# Nucleo.net
KiCad netlist of a schematic drawn in Altium Designer
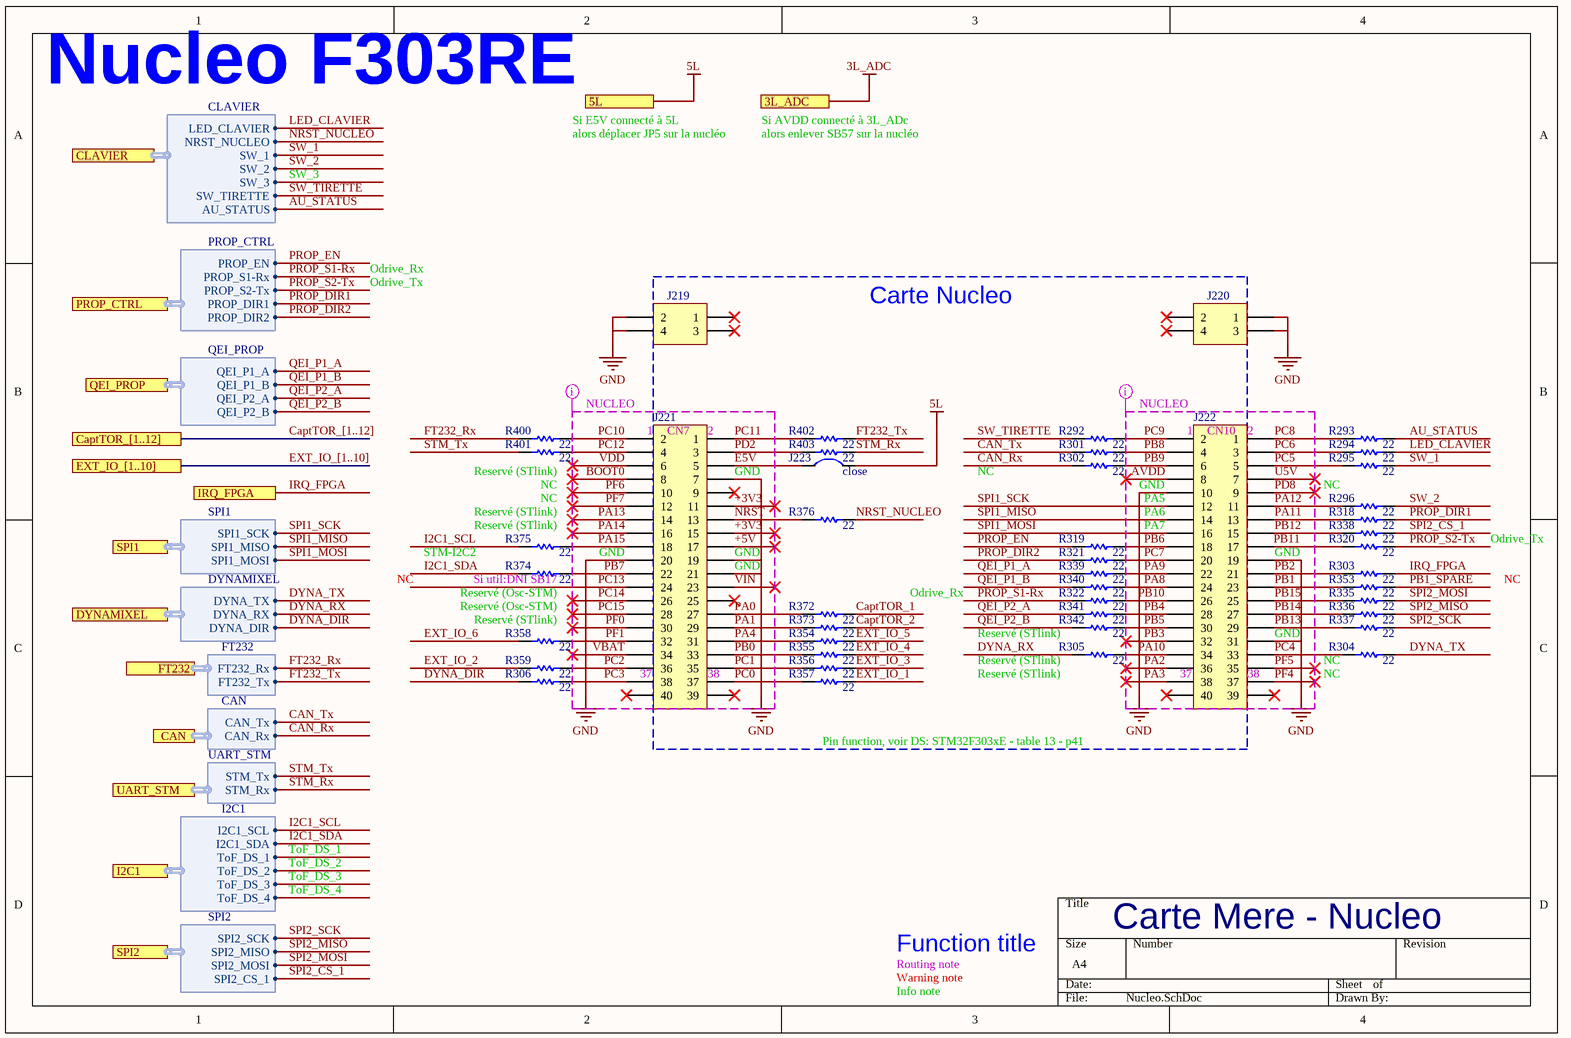
[diagram p0: Nucleo.SchDoc]

(export (version "E")
  (design (tool "Eeschema 10.0.6"))
  (components
    (comp (ref "J219")
      (value "61000421821")
      (footprint "61000421821")
      (description "WR-PHD Socket Header, SMT, pitch 2.54mm, Dual Row, Vertical, 4p")
      (fields (field (name "MANUFACTURER") "Wurth Elektronik"))
      (libsource (lib "Connecteurs") (part "61000421821"))
    )
    (comp (ref "J220")
      (value "61000421821")
      (footprint "61000421821")
      (description "WR-PHD Socket Header, SMT, pitch 2.54mm, Dual Row, Vertical, 4p")
      (fields (field (name "MANUFACTURER") "Wurth Elektronik"))
      (libsource (lib "Connecteurs") (part "61000421821"))
    )
    (comp (ref "J221")
      (value "61004021821")
      (footprint "61004021821")
      (description "WR-PHD Socket Header, SMT, pitch 2.54mm, Dual Row, Vertical, 40p")
      (fields (field (name "MANUFACTURER") "Wurth Elektronik"))
      (libsource (lib "Connecteurs") (part "61004021821"))
    )
    (comp (ref "J222")
      (value "61004021821")
      (footprint "61004021821")
      (description "WR-PHD Socket Header, SMT, pitch 2.54mm, Dual Row, Vertical, 40p")
      (fields (field (name "MANUFACTURER") "Wurth Elektronik"))
      (libsource (lib "Connecteurs") (part "61004021821"))
    )
    (comp (ref "J223")
      (value "close")
      (footprint "CAVALIER_0603_C")
      (description "Cavalier soudure \"fermé\" + empreinte dipole 0603")
      (libsource (lib "Divers") (part "CAVALIER_0603_C"))
    )
    (comp (ref "R292")
      (value "22")
      (footprint "RESC1005X04N")
      (description "RES SMD 22 OHM 1% 1/16W 0402")
      (fields (field (name "POWER") "63mW") (field (name "MANUFACTURER") "Yageo"))
      (libsource (lib "Resistance") (part "RC0402FR-0722RL"))
    )
    (comp (ref "R293")
      (value "22")
      (footprint "RESC1005X04N")
      (description "RES SMD 22 OHM 1% 1/16W 0402")
      (fields (field (name "POWER") "63mW") (field (name "MANUFACTURER") "Yageo"))
      (libsource (lib "Resistance") (part "RC0402FR-0722RL"))
    )
    (comp (ref "R294")
      (value "22")
      (footprint "RESC1005X04N")
      (description "RES SMD 22 OHM 1% 1/16W 0402")
      (fields (field (name "POWER") "63mW") (field (name "MANUFACTURER") "Yageo"))
      (libsource (lib "Resistance") (part "RC0402FR-0722RL"))
    )
    (comp (ref "R295")
      (value "22")
      (footprint "RESC1005X04N")
      (description "RES SMD 22 OHM 1% 1/16W 0402")
      (fields (field (name "POWER") "63mW") (field (name "MANUFACTURER") "Yageo"))
      (libsource (lib "Resistance") (part "RC0402FR-0722RL"))
    )
    (comp (ref "R296")
      (value "22")
      (footprint "RESC1005X04N")
      (description "RES SMD 22 OHM 1% 1/16W 0402")
      (fields (field (name "POWER") "63mW") (field (name "MANUFACTURER") "Yageo"))
      (libsource (lib "Resistance") (part "RC0402FR-0722RL"))
    )
    (comp (ref "R301")
      (value "22")
      (footprint "RESC1005X04N")
      (description "RES SMD 22 OHM 1% 1/16W 0402")
      (fields (field (name "POWER") "63mW") (field (name "MANUFACTURER") "Yageo"))
      (libsource (lib "Resistance") (part "RC0402FR-0722RL"))
    )
    (comp (ref "R302")
      (value "22")
      (footprint "RESC1005X04N")
      (description "RES SMD 22 OHM 1% 1/16W 0402")
      (fields (field (name "POWER") "63mW") (field (name "MANUFACTURER") "Yageo"))
      (libsource (lib "Resistance") (part "RC0402FR-0722RL"))
    )
    (comp (ref "R303")
      (value "22")
      (footprint "RESC1005X04N")
      (description "RES SMD 22 OHM 1% 1/16W 0402")
      (fields (field (name "POWER") "63mW") (field (name "MANUFACTURER") "Yageo"))
      (libsource (lib "Resistance") (part "RC0402FR-0722RL"))
    )
    (comp (ref "R304")
      (value "22")
      (footprint "RESC1005X04N")
      (description "RES SMD 22 OHM 1% 1/16W 0402")
      (fields (field (name "POWER") "63mW") (field (name "MANUFACTURER") "Yageo"))
      (libsource (lib "Resistance") (part "RC0402FR-0722RL"))
    )
    (comp (ref "R305")
      (value "22")
      (footprint "RESC1005X04N")
      (description "RES SMD 22 OHM 1% 1/16W 0402")
      (fields (field (name "POWER") "63mW") (field (name "MANUFACTURER") "Yageo"))
      (libsource (lib "Resistance") (part "RC0402FR-0722RL"))
    )
    (comp (ref "R306")
      (value "22")
      (footprint "RESC1005X04N")
      (description "RES SMD 22 OHM 1% 1/16W 0402")
      (fields (field (name "POWER") "63mW") (field (name "MANUFACTURER") "Yageo"))
      (libsource (lib "Resistance") (part "RC0402FR-0722RL"))
    )
    (comp (ref "R318")
      (value "22")
      (footprint "RESC1005X04N")
      (description "RES SMD 22 OHM 1% 1/16W 0402")
      (fields (field (name "POWER") "63mW") (field (name "MANUFACTURER") "Yageo"))
      (libsource (lib "Resistance") (part "RC0402FR-0722RL"))
    )
    (comp (ref "R319")
      (value "22")
      (footprint "RESC1005X04N")
      (description "RES SMD 22 OHM 1% 1/16W 0402")
      (fields (field (name "POWER") "63mW") (field (name "MANUFACTURER") "Yageo"))
      (libsource (lib "Resistance") (part "RC0402FR-0722RL"))
    )
    (comp (ref "R320")
      (value "22")
      (footprint "RESC1005X04N")
      (description "RES SMD 22 OHM 1% 1/16W 0402")
      (fields (field (name "POWER") "63mW") (field (name "MANUFACTURER") "Yageo"))
      (libsource (lib "Resistance") (part "RC0402FR-0722RL"))
    )
    (comp (ref "R321")
      (value "22")
      (footprint "RESC1005X04N")
      (description "RES SMD 22 OHM 1% 1/16W 0402")
      (fields (field (name "POWER") "63mW") (field (name "MANUFACTURER") "Yageo"))
      (libsource (lib "Resistance") (part "RC0402FR-0722RL"))
    )
    (comp (ref "R322")
      (value "22")
      (footprint "RESC1005X04N")
      (description "RES SMD 22 OHM 1% 1/16W 0402")
      (fields (field (name "POWER") "63mW") (field (name "MANUFACTURER") "Yageo"))
      (libsource (lib "Resistance") (part "RC0402FR-0722RL"))
    )
    (comp (ref "R335")
      (value "22")
      (footprint "RESC1005X04N")
      (description "RES SMD 22 OHM 1% 1/16W 0402")
      (fields (field (name "POWER") "63mW") (field (name "MANUFACTURER") "Yageo"))
      (libsource (lib "Resistance") (part "RC0402FR-0722RL"))
    )
    (comp (ref "R336")
      (value "22")
      (footprint "RESC1005X04N")
      (description "RES SMD 22 OHM 1% 1/16W 0402")
      (fields (field (name "POWER") "63mW") (field (name "MANUFACTURER") "Yageo"))
      (libsource (lib "Resistance") (part "RC0402FR-0722RL"))
    )
    (comp (ref "R337")
      (value "22")
      (footprint "RESC1005X04N")
      (description "RES SMD 22 OHM 1% 1/16W 0402")
      (fields (field (name "POWER") "63mW") (field (name "MANUFACTURER") "Yageo"))
      (libsource (lib "Resistance") (part "RC0402FR-0722RL"))
    )
    (comp (ref "R338")
      (value "22")
      (footprint "RESC1005X04N")
      (description "RES SMD 22 OHM 1% 1/16W 0402")
      (fields (field (name "POWER") "63mW") (field (name "MANUFACTURER") "Yageo"))
      (libsource (lib "Resistance") (part "RC0402FR-0722RL"))
    )
    (comp (ref "R339")
      (value "22")
      (footprint "RESC1005X04N")
      (description "RES SMD 22 OHM 1% 1/16W 0402")
      (fields (field (name "POWER") "63mW") (field (name "MANUFACTURER") "Yageo"))
      (libsource (lib "Resistance") (part "RC0402FR-0722RL"))
    )
    (comp (ref "R340")
      (value "22")
      (footprint "RESC1005X04N")
      (description "RES SMD 22 OHM 1% 1/16W 0402")
      (fields (field (name "POWER") "63mW") (field (name "MANUFACTURER") "Yageo"))
      (libsource (lib "Resistance") (part "RC0402FR-0722RL"))
    )
    (comp (ref "R341")
      (value "22")
      (footprint "RESC1005X04N")
      (description "RES SMD 22 OHM 1% 1/16W 0402")
      (fields (field (name "POWER") "63mW") (field (name "MANUFACTURER") "Yageo"))
      (libsource (lib "Resistance") (part "RC0402FR-0722RL"))
    )
    (comp (ref "R342")
      (value "22")
      (footprint "RESC1005X04N")
      (description "RES SMD 22 OHM 1% 1/16W 0402")
      (fields (field (name "POWER") "63mW") (field (name "MANUFACTURER") "Yageo"))
      (libsource (lib "Resistance") (part "RC0402FR-0722RL"))
    )
    (comp (ref "R353")
      (value "22")
      (footprint "RESC1005X04N")
      (description "RES SMD 22 OHM 1% 1/16W 0402")
      (fields (field (name "POWER") "63mW") (field (name "MANUFACTURER") "Yageo"))
      (libsource (lib "Resistance") (part "RC0402FR-0722RL"))
    )
    (comp (ref "R354")
      (value "22")
      (footprint "RESC1005X04N")
      (description "RES SMD 22 OHM 1% 1/16W 0402")
      (fields (field (name "POWER") "63mW") (field (name "MANUFACTURER") "Yageo"))
      (libsource (lib "Resistance") (part "RC0402FR-0722RL"))
    )
    (comp (ref "R355")
      (value "22")
      (footprint "RESC1005X04N")
      (description "RES SMD 22 OHM 1% 1/16W 0402")
      (fields (field (name "POWER") "63mW") (field (name "MANUFACTURER") "Yageo"))
      (libsource (lib "Resistance") (part "RC0402FR-0722RL"))
    )
    (comp (ref "R356")
      (value "22")
      (footprint "RESC1005X04N")
      (description "RES SMD 22 OHM 1% 1/16W 0402")
      (fields (field (name "POWER") "63mW") (field (name "MANUFACTURER") "Yageo"))
      (libsource (lib "Resistance") (part "RC0402FR-0722RL"))
    )
    (comp (ref "R357")
      (value "22")
      (footprint "RESC1005X04N")
      (description "RES SMD 22 OHM 1% 1/16W 0402")
      (fields (field (name "POWER") "63mW") (field (name "MANUFACTURER") "Yageo"))
      (libsource (lib "Resistance") (part "RC0402FR-0722RL"))
    )
    (comp (ref "R358")
      (value "22")
      (footprint "RESC1005X04N")
      (description "RES SMD 22 OHM 1% 1/16W 0402")
      (fields (field (name "POWER") "63mW") (field (name "MANUFACTURER") "Yageo"))
      (libsource (lib "Resistance") (part "RC0402FR-0722RL"))
    )
    (comp (ref "R359")
      (value "22")
      (footprint "RESC1005X04N")
      (description "RES SMD 22 OHM 1% 1/16W 0402")
      (fields (field (name "POWER") "63mW") (field (name "MANUFACTURER") "Yageo"))
      (libsource (lib "Resistance") (part "RC0402FR-0722RL"))
    )
    (comp (ref "R372")
      (value "22")
      (footprint "RESC1005X04N")
      (description "RES SMD 22 OHM 1% 1/16W 0402")
      (fields (field (name "POWER") "63mW") (field (name "MANUFACTURER") "Yageo"))
      (libsource (lib "Resistance") (part "RC0402FR-0722RL"))
    )
    (comp (ref "R373")
      (value "22")
      (footprint "RESC1005X04N")
      (description "RES SMD 22 OHM 1% 1/16W 0402")
      (fields (field (name "POWER") "63mW") (field (name "MANUFACTURER") "Yageo"))
      (libsource (lib "Resistance") (part "RC0402FR-0722RL"))
    )
    (comp (ref "R374")
      (value "22")
      (footprint "RESC1005X04N")
      (description "RES SMD 22 OHM 1% 1/16W 0402")
      (fields (field (name "POWER") "63mW") (field (name "MANUFACTURER") "Yageo"))
      (libsource (lib "Resistance") (part "RC0402FR-0722RL"))
    )
    (comp (ref "R375")
      (value "22")
      (footprint "RESC1005X04N")
      (description "RES SMD 22 OHM 1% 1/16W 0402")
      (fields (field (name "POWER") "63mW") (field (name "MANUFACTURER") "Yageo"))
      (libsource (lib "Resistance") (part "RC0402FR-0722RL"))
    )
    (comp (ref "R376")
      (value "22")
      (footprint "RESC1005X04N")
      (description "RES SMD 22 OHM 1% 1/16W 0402")
      (fields (field (name "POWER") "63mW") (field (name "MANUFACTURER") "Yageo"))
      (libsource (lib "Resistance") (part "RC0402FR-0722RL"))
    )
    (comp (ref "R400")
      (value "22")
      (footprint "RESC1005X04N")
      (description "RES SMD 22 OHM 1% 1/16W 0402")
      (fields (field (name "POWER") "63mW") (field (name "MANUFACTURER") "Yageo"))
      (libsource (lib "Resistance") (part "RC0402FR-0722RL"))
    )
    (comp (ref "R401")
      (value "22")
      (footprint "RESC1005X04N")
      (description "RES SMD 22 OHM 1% 1/16W 0402")
      (fields (field (name "POWER") "63mW") (field (name "MANUFACTURER") "Yageo"))
      (libsource (lib "Resistance") (part "RC0402FR-0722RL"))
    )
    (comp (ref "R402")
      (value "22")
      (footprint "RESC1005X04N")
      (description "RES SMD 22 OHM 1% 1/16W 0402")
      (fields (field (name "POWER") "63mW") (field (name "MANUFACTURER") "Yageo"))
      (libsource (lib "Resistance") (part "RC0402FR-0722RL"))
    )
    (comp (ref "R403")
      (value "22")
      (footprint "RESC1005X04N")
      (description "RES SMD 22 OHM 1% 1/16W 0402")
      (fields (field (name "POWER") "63mW") (field (name "MANUFACTURER") "Yageo"))
      (libsource (lib "Resistance") (part "RC0402FR-0722RL"))
    )
  )
  (nets
    (net (code "25") (name "/+3V3") (class "Default")
      (node (ref "J221") (pin "11") (pinfunction "11_11") (pintype "passive"))
      (node (ref "J221") (pin "15") (pinfunction "15_15") (pintype "passive"))
    )
    (net (code "26") (name "/+5V") (class "Default")
      (node (ref "J221") (pin "17") (pinfunction "17_17") (pintype "passive+no_connect"))
    )
    (net (code "27") (name "/AU_STATUS") (class "Default")
      (node (ref "R293") (pin "2") (pinfunction "2_2") (pintype "passive"))
    )
    (net (code "28") (name "/AVDD") (class "Default")
      (node (ref "J222") (pin "8") (pinfunction "8_8") (pintype "passive+no_connect"))
    )
    (net (code "29") (name "/BOOT0") (class "Default")
      (node (ref "J221") (pin "8") (pinfunction "8_8") (pintype "passive+no_connect"))
    )
    (net (code "30") (name "/CAN_Rx") (class "Default")
      (node (ref "R302") (pin "1") (pinfunction "1_1") (pintype "passive"))
    )
    (net (code "31") (name "/CAN_Tx") (class "Default")
      (node (ref "R301") (pin "1") (pinfunction "1_1") (pintype "passive"))
    )
    (net (code "32") (name "/CaptTOR_1") (class "Default")
      (node (ref "R372") (pin "2") (pinfunction "2_2") (pintype "passive"))
    )
    (net (code "33") (name "/CaptTOR_2") (class "Default")
      (node (ref "R373") (pin "2") (pinfunction "2_2") (pintype "passive"))
    )
    (net (code "35") (name "/DYNA_DIR") (class "Default")
      (node (ref "R306") (pin "1") (pinfunction "1_1") (pintype "passive"))
    )
    (net (code "36") (name "/DYNA_RX") (class "Default")
      (node (ref "R305") (pin "1") (pinfunction "1_1") (pintype "passive"))
    )
    (net (code "37") (name "/DYNA_TX") (class "Default")
      (node (ref "R304") (pin "2") (pinfunction "2_2") (pintype "passive"))
    )
    (net (code "38") (name "/E5V") (class "Default")
      (node (ref "J221") (pin "5") (pinfunction "5_5") (pintype "passive"))
      (node (ref "J223") (pin "1") (pinfunction "1_1") (pintype "passive"))
    )
    (net (code "39") (name "/EXT_IO_1") (class "Default")
      (node (ref "R357") (pin "2") (pinfunction "2_2") (pintype "passive"))
    )
    (net (code "40") (name "/EXT_IO_2") (class "Default")
      (node (ref "R359") (pin "1") (pinfunction "1_1") (pintype "passive"))
    )
    (net (code "41") (name "/EXT_IO_3") (class "Default")
      (node (ref "R356") (pin "2") (pinfunction "2_2") (pintype "passive"))
    )
    (net (code "42") (name "/EXT_IO_4") (class "Default")
      (node (ref "R355") (pin "2") (pinfunction "2_2") (pintype "passive"))
    )
    (net (code "43") (name "/EXT_IO_5") (class "Default")
      (node (ref "R354") (pin "2") (pinfunction "2_2") (pintype "passive"))
    )
    (net (code "44") (name "/EXT_IO_6") (class "Default")
      (node (ref "R358") (pin "1") (pinfunction "1_1") (pintype "passive"))
    )
    (net (code "46") (name "/FT232_Rx") (class "Default")
      (node (ref "R400") (pin "1") (pinfunction "1_1") (pintype "passive"))
    )
    (net (code "47") (name "/FT232_Tx") (class "Default")
      (node (ref "R402") (pin "2") (pinfunction "2_2") (pintype "passive"))
    )
    (net (code "48") (name "/I2C1_SCL") (class "Default")
      (node (ref "R375") (pin "1") (pinfunction "1_1") (pintype "passive"))
    )
    (net (code "49") (name "/I2C1_SDA") (class "Default")
      (node (ref "R374") (pin "1") (pinfunction "1_1") (pintype "passive"))
    )
    (net (code "50") (name "/IRQ_FPGA") (class "Default")
      (node (ref "R303") (pin "2") (pinfunction "2_2") (pintype "passive"))
    )
    (net (code "51") (name "/LED_CLAVIER") (class "Default")
      (node (ref "R294") (pin "2") (pinfunction "2_2") (pintype "passive"))
    )
    (net (code "52") (name "/NRST") (class "Default")
      (node (ref "J221") (pin "13") (pinfunction "13_13") (pintype "passive"))
      (node (ref "R376") (pin "1") (pinfunction "1_1") (pintype "passive"))
    )
    (net (code "53") (name "/NRST_NUCLEO") (class "Default")
      (node (ref "R376") (pin "2") (pinfunction "2_2") (pintype "passive"))
    )
    (net (code "54") (name "/PA0") (class "Default")
      (node (ref "J221") (pin "27") (pinfunction "27_27") (pintype "passive"))
      (node (ref "R372") (pin "1") (pinfunction "1_1") (pintype "passive"))
    )
    (net (code "55") (name "/PA1") (class "Default")
      (node (ref "J221") (pin "29") (pinfunction "29_29") (pintype "passive"))
      (node (ref "R373") (pin "1") (pinfunction "1_1") (pintype "passive"))
    )
    (net (code "56") (name "/PA2") (class "Default")
      (node (ref "J222") (pin "36") (pinfunction "36_36") (pintype "passive+no_connect"))
    )
    (net (code "57") (name "/PA3") (class "Default")
      (node (ref "J222") (pin "38") (pinfunction "38_38") (pintype "passive+no_connect"))
    )
    (net (code "58") (name "/PA4") (class "Default")
      (node (ref "J221") (pin "31") (pinfunction "31_31") (pintype "passive"))
      (node (ref "R354") (pin "1") (pinfunction "1_1") (pintype "passive"))
    )
    (net (code "59") (name "/PA8") (class "Default")
      (node (ref "J222") (pin "24") (pinfunction "24_24") (pintype "passive"))
      (node (ref "R340") (pin "2") (pinfunction "2_2") (pintype "passive"))
    )
    (net (code "60") (name "/PA9") (class "Default")
      (node (ref "J222") (pin "22") (pinfunction "22_22") (pintype "passive"))
      (node (ref "R339") (pin "2") (pinfunction "2_2") (pintype "passive"))
    )
    (net (code "61") (name "/PA10") (class "Default")
      (node (ref "J222") (pin "34") (pinfunction "34_34") (pintype "passive"))
      (node (ref "R305") (pin "2") (pinfunction "2_2") (pintype "passive"))
    )
    (net (code "62") (name "/PA11") (class "Default")
      (node (ref "J222") (pin "13") (pinfunction "13_13") (pintype "passive"))
      (node (ref "R318") (pin "1") (pinfunction "1_1") (pintype "passive"))
    )
    (net (code "63") (name "/PA12") (class "Default")
      (node (ref "J222") (pin "11") (pinfunction "11_11") (pintype "passive"))
      (node (ref "R296") (pin "1") (pinfunction "1_1") (pintype "passive"))
    )
    (net (code "64") (name "/PA13") (class "Default")
      (node (ref "J221") (pin "14") (pinfunction "14_14") (pintype "passive+no_connect"))
    )
    (net (code "65") (name "/PA14") (class "Default")
      (node (ref "J221") (pin "16") (pinfunction "16_16") (pintype "passive+no_connect"))
    )
    (net (code "66") (name "/PA15") (class "Default")
      (node (ref "J221") (pin "18") (pinfunction "18_18") (pintype "passive"))
      (node (ref "R375") (pin "2") (pinfunction "2_2") (pintype "passive"))
    )
    (net (code "67") (name "/PB0") (class "Default")
      (node (ref "J221") (pin "33") (pinfunction "33_33") (pintype "passive"))
      (node (ref "R355") (pin "1") (pinfunction "1_1") (pintype "passive"))
    )
    (net (code "68") (name "/PB1") (class "Default")
      (node (ref "J222") (pin "23") (pinfunction "23_23") (pintype "passive"))
      (node (ref "R353") (pin "1") (pinfunction "1_1") (pintype "passive"))
    )
    (net (code "69") (name "/PB1_SPARE") (class "Default")
      (node (ref "R353") (pin "2") (pinfunction "2_2") (pintype "passive"))
    )
    (net (code "70") (name "/PB2") (class "Default")
      (node (ref "J222") (pin "21") (pinfunction "21_21") (pintype "passive"))
      (node (ref "R303") (pin "1") (pinfunction "1_1") (pintype "passive"))
    )
    (net (code "71") (name "/PB3") (class "Default")
      (node (ref "J222") (pin "32") (pinfunction "32_32") (pintype "passive+no_connect"))
    )
    (net (code "72") (name "/PB4") (class "Default")
      (node (ref "J222") (pin "28") (pinfunction "28_28") (pintype "passive"))
      (node (ref "R341") (pin "2") (pinfunction "2_2") (pintype "passive"))
    )
    (net (code "73") (name "/PB5") (class "Default")
      (node (ref "J222") (pin "30") (pinfunction "30_30") (pintype "passive"))
      (node (ref "R342") (pin "2") (pinfunction "2_2") (pintype "passive"))
    )
    (net (code "74") (name "/PB6") (class "Default")
      (node (ref "J222") (pin "18") (pinfunction "18_18") (pintype "passive"))
      (node (ref "R319") (pin "2") (pinfunction "2_2") (pintype "passive"))
    )
    (net (code "75") (name "/PB7") (class "Default")
      (node (ref "J221") (pin "22") (pinfunction "22_22") (pintype "passive"))
      (node (ref "R374") (pin "2") (pinfunction "2_2") (pintype "passive"))
    )
    (net (code "76") (name "/PB8") (class "Default")
      (node (ref "J222") (pin "4") (pinfunction "4_4") (pintype "passive"))
      (node (ref "R301") (pin "2") (pinfunction "2_2") (pintype "passive"))
    )
    (net (code "77") (name "/PB9") (class "Default")
      (node (ref "J222") (pin "6") (pinfunction "6_6") (pintype "passive"))
      (node (ref "R302") (pin "2") (pinfunction "2_2") (pintype "passive"))
    )
    (net (code "78") (name "/PB10") (class "Default")
      (node (ref "J222") (pin "26") (pinfunction "26_26") (pintype "passive"))
      (node (ref "R322") (pin "2") (pinfunction "2_2") (pintype "passive"))
    )
    (net (code "79") (name "/PB11") (class "Default")
      (node (ref "J222") (pin "17") (pinfunction "17_17") (pintype "passive"))
      (node (ref "R320") (pin "1") (pinfunction "1_1") (pintype "passive"))
    )
    (net (code "80") (name "/PB12") (class "Default")
      (node (ref "J222") (pin "15") (pinfunction "15_15") (pintype "passive"))
      (node (ref "R338") (pin "1") (pinfunction "1_1") (pintype "passive"))
    )
    (net (code "81") (name "/PB13") (class "Default")
      (node (ref "J222") (pin "29") (pinfunction "29_29") (pintype "passive"))
      (node (ref "R337") (pin "1") (pinfunction "1_1") (pintype "passive"))
    )
    (net (code "82") (name "/PB14") (class "Default")
      (node (ref "J222") (pin "27") (pinfunction "27_27") (pintype "passive"))
      (node (ref "R336") (pin "1") (pinfunction "1_1") (pintype "passive"))
    )
    (net (code "83") (name "/PB15") (class "Default")
      (node (ref "J222") (pin "25") (pinfunction "25_25") (pintype "passive"))
      (node (ref "R335") (pin "1") (pinfunction "1_1") (pintype "passive"))
    )
    (net (code "84") (name "/PC0") (class "Default")
      (node (ref "J221") (pin "37") (pinfunction "37_37") (pintype "passive"))
      (node (ref "R357") (pin "1") (pinfunction "1_1") (pintype "passive"))
    )
    (net (code "85") (name "/PC1") (class "Default")
      (node (ref "J221") (pin "35") (pinfunction "35_35") (pintype "passive"))
      (node (ref "R356") (pin "1") (pinfunction "1_1") (pintype "passive"))
    )
    (net (code "86") (name "/PC2") (class "Default")
      (node (ref "J221") (pin "36") (pinfunction "36_36") (pintype "passive"))
      (node (ref "R359") (pin "2") (pinfunction "2_2") (pintype "passive"))
    )
    (net (code "87") (name "/PC3") (class "Default")
      (node (ref "J221") (pin "38") (pinfunction "38_38") (pintype "passive"))
      (node (ref "R306") (pin "2") (pinfunction "2_2") (pintype "passive"))
    )
    (net (code "88") (name "/PC4") (class "Default")
      (node (ref "J222") (pin "33") (pinfunction "33_33") (pintype "passive"))
      (node (ref "R304") (pin "1") (pinfunction "1_1") (pintype "passive"))
    )
    (net (code "89") (name "/PC5") (class "Default")
      (node (ref "J222") (pin "5") (pinfunction "5_5") (pintype "passive"))
      (node (ref "R295") (pin "1") (pinfunction "1_1") (pintype "passive"))
    )
    (net (code "90") (name "/PC6") (class "Default")
      (node (ref "J222") (pin "3") (pinfunction "3_3") (pintype "passive"))
      (node (ref "R294") (pin "1") (pinfunction "1_1") (pintype "passive"))
    )
    (net (code "91") (name "/PC7") (class "Default")
      (node (ref "J222") (pin "20") (pinfunction "20_20") (pintype "passive"))
      (node (ref "R321") (pin "2") (pinfunction "2_2") (pintype "passive"))
    )
    (net (code "92") (name "/PC8") (class "Default")
      (node (ref "J222") (pin "1") (pinfunction "1_1") (pintype "passive"))
      (node (ref "R293") (pin "1") (pinfunction "1_1") (pintype "passive"))
    )
    (net (code "93") (name "/PC9") (class "Default")
      (node (ref "J222") (pin "2") (pinfunction "2_2") (pintype "passive"))
      (node (ref "R292") (pin "2") (pinfunction "2_2") (pintype "passive"))
    )
    (net (code "94") (name "/PC10") (class "Default")
      (node (ref "J221") (pin "2") (pinfunction "2_2") (pintype "passive"))
      (node (ref "R400") (pin "2") (pinfunction "2_2") (pintype "passive"))
    )
    (net (code "95") (name "/PC11") (class "Default")
      (node (ref "J221") (pin "1") (pinfunction "1_1") (pintype "passive"))
      (node (ref "R402") (pin "1") (pinfunction "1_1") (pintype "passive"))
    )
    (net (code "96") (name "/PC12") (class "Default")
      (node (ref "J221") (pin "4") (pinfunction "4_4") (pintype "passive"))
      (node (ref "R401") (pin "2") (pinfunction "2_2") (pintype "passive"))
    )
    (net (code "97") (name "/PC13") (class "Default")
      (node (ref "J221") (pin "24") (pinfunction "24_24") (pintype "passive"))
    )
    (net (code "98") (name "/PC14") (class "Default")
      (node (ref "J221") (pin "26") (pinfunction "26_26") (pintype "passive+no_connect"))
    )
    (net (code "99") (name "/PC15") (class "Default")
      (node (ref "J221") (pin "28") (pinfunction "28_28") (pintype "passive+no_connect"))
    )
    (net (code "100") (name "/PD2") (class "Default")
      (node (ref "J221") (pin "3") (pinfunction "3_3") (pintype "passive"))
      (node (ref "R403") (pin "1") (pinfunction "1_1") (pintype "passive"))
    )
    (net (code "101") (name "/PD8") (class "Default")
      (node (ref "J222") (pin "9") (pinfunction "9_9") (pintype "passive+no_connect"))
    )
    (net (code "102") (name "/PF0") (class "Default")
      (node (ref "J221") (pin "30") (pinfunction "30_30") (pintype "passive+no_connect"))
    )
    (net (code "103") (name "/PF1") (class "Default")
      (node (ref "J221") (pin "32") (pinfunction "32_32") (pintype "passive"))
      (node (ref "R358") (pin "2") (pinfunction "2_2") (pintype "passive"))
    )
    (net (code "104") (name "/PF4") (class "Default")
      (node (ref "J222") (pin "37") (pinfunction "37_37") (pintype "passive+no_connect"))
    )
    (net (code "105") (name "/PF5") (class "Default")
      (node (ref "J222") (pin "35") (pinfunction "35_35") (pintype "passive+no_connect"))
    )
    (net (code "106") (name "/PF6") (class "Default")
      (node (ref "J221") (pin "10") (pinfunction "10_10") (pintype "passive+no_connect"))
    )
    (net (code "107") (name "/PF7") (class "Default")
      (node (ref "J221") (pin "12") (pinfunction "12_12") (pintype "passive+no_connect"))
    )
    (net (code "108") (name "/PROP_DIR1") (class "Default")
      (node (ref "R318") (pin "2") (pinfunction "2_2") (pintype "passive"))
    )
    (net (code "109") (name "/PROP_DIR2") (class "Default")
      (node (ref "R321") (pin "1") (pinfunction "1_1") (pintype "passive"))
    )
    (net (code "110") (name "/PROP_EN") (class "Default")
      (node (ref "R319") (pin "1") (pinfunction "1_1") (pintype "passive"))
    )
    (net (code "111") (name "/PROP_S1-Rx") (class "Default")
      (node (ref "R322") (pin "1") (pinfunction "1_1") (pintype "passive"))
    )
    (net (code "112") (name "/PROP_S2-Tx") (class "Default")
      (node (ref "R320") (pin "2") (pinfunction "2_2") (pintype "passive"))
    )
    (net (code "113") (name "/QEI_P1_A") (class "Default")
      (node (ref "R339") (pin "1") (pinfunction "1_1") (pintype "passive"))
    )
    (net (code "114") (name "/QEI_P1_B") (class "Default")
      (node (ref "R340") (pin "1") (pinfunction "1_1") (pintype "passive"))
    )
    (net (code "115") (name "/QEI_P2_A") (class "Default")
      (node (ref "R341") (pin "1") (pinfunction "1_1") (pintype "passive"))
    )
    (net (code "116") (name "/QEI_P2_B") (class "Default")
      (node (ref "R342") (pin "1") (pinfunction "1_1") (pintype "passive"))
    )
    (net (code "117") (name "/SPI1_MISO") (class "Default")
      (node (ref "J222") (pin "14") (pinfunction "14_14") (pintype "passive"))
    )
    (net (code "118") (name "/SPI1_MOSI") (class "Default")
      (node (ref "J222") (pin "16") (pinfunction "16_16") (pintype "passive"))
    )
    (net (code "119") (name "/SPI1_SCK") (class "Default")
      (node (ref "J222") (pin "12") (pinfunction "12_12") (pintype "passive"))
    )
    (net (code "120") (name "/SPI2_CS_1") (class "Default")
      (node (ref "R338") (pin "2") (pinfunction "2_2") (pintype "passive"))
    )
    (net (code "121") (name "/SPI2_MISO") (class "Default")
      (node (ref "R336") (pin "2") (pinfunction "2_2") (pintype "passive"))
    )
    (net (code "122") (name "/SPI2_MOSI") (class "Default")
      (node (ref "R335") (pin "2") (pinfunction "2_2") (pintype "passive"))
    )
    (net (code "123") (name "/SPI2_SCK") (class "Default")
      (node (ref "R337") (pin "2") (pinfunction "2_2") (pintype "passive"))
    )
    (net (code "124") (name "/STM_Rx") (class "Default")
      (node (ref "R403") (pin "2") (pinfunction "2_2") (pintype "passive"))
    )
    (net (code "125") (name "/STM_Tx") (class "Default")
      (node (ref "R401") (pin "1") (pinfunction "1_1") (pintype "passive"))
    )
    (net (code "126") (name "/SW_1") (class "Default")
      (node (ref "R295") (pin "2") (pinfunction "2_2") (pintype "passive"))
    )
    (net (code "127") (name "/SW_2") (class "Default")
      (node (ref "R296") (pin "2") (pinfunction "2_2") (pintype "passive"))
    )
    (net (code "128") (name "/SW_TIRETTE") (class "Default")
      (node (ref "R292") (pin "1") (pinfunction "1_1") (pintype "passive"))
    )
    (net (code "129") (name "/U5V") (class "Default")
      (node (ref "J222") (pin "7") (pinfunction "7_7") (pintype "passive+no_connect"))
    )
    (net (code "130") (name "/VBAT") (class "Default")
      (node (ref "J221") (pin "34") (pinfunction "34_34") (pintype "passive+no_connect"))
    )
    (net (code "131") (name "/VDD") (class "Default")
      (node (ref "J221") (pin "6") (pinfunction "6_6") (pintype "passive+no_connect"))
    )
    (net (code "132") (name "/VIN") (class "Default")
      (node (ref "J221") (pin "23") (pinfunction "23_23") (pintype "passive+no_connect"))
    )
    (net (code "144") (name "5L") (class "Default")
      (node (ref "J223") (pin "2") (pinfunction "2_2") (pintype "passive"))
    )
    (net (code "145") (name "GND") (class "Default")
      (node (ref "J219") (pin "2") (pinfunction "2_2") (pintype "passive"))
      (node (ref "J219") (pin "4") (pinfunction "4_4") (pintype "passive"))
      (node (ref "J220") (pin "1") (pinfunction "1_1") (pintype "passive"))
      (node (ref "J220") (pin "3") (pinfunction "3_3") (pintype "passive"))
      (node (ref "J221") (pin "19") (pinfunction "19_19") (pintype "passive"))
      (node (ref "J221") (pin "20") (pinfunction "20_20") (pintype "passive"))
      (node (ref "J221") (pin "21") (pinfunction "21_21") (pintype "passive"))
      (node (ref "J221") (pin "7") (pinfunction "7_7") (pintype "passive"))
      (node (ref "J222") (pin "10") (pinfunction "10_10") (pintype "passive"))
      (node (ref "J222") (pin "19") (pinfunction "19_19") (pintype "passive"))
      (node (ref "J222") (pin "31") (pinfunction "31_31") (pintype "passive"))
    )
    (net (code "146") (name "unconnected-(J219-Pad1)") (class "Default")
      (node (ref "J219") (pin "1") (pinfunction "1_1") (pintype "passive+no_connect"))
    )
    (net (code "147") (name "unconnected-(J219-Pad3)") (class "Default")
      (node (ref "J219") (pin "3") (pinfunction "3_3") (pintype "passive+no_connect"))
    )
    (net (code "148") (name "unconnected-(J220-Pad2)") (class "Default")
      (node (ref "J220") (pin "2") (pinfunction "2_2") (pintype "passive+no_connect"))
    )
    (net (code "149") (name "unconnected-(J220-Pad4)") (class "Default")
      (node (ref "J220") (pin "4") (pinfunction "4_4") (pintype "passive+no_connect"))
    )
    (net (code "150") (name "unconnected-(J221-Pad9)") (class "Default")
      (node (ref "J221") (pin "9") (pinfunction "9_9") (pintype "passive+no_connect"))
    )
    (net (code "151") (name "unconnected-(J221-Pad25)") (class "Default")
      (node (ref "J221") (pin "25") (pinfunction "25_25") (pintype "passive+no_connect"))
    )
    (net (code "152") (name "unconnected-(J221-Pad39)") (class "Default")
      (node (ref "J221") (pin "39") (pinfunction "39_39") (pintype "passive+no_connect"))
    )
    (net (code "153") (name "unconnected-(J221-Pad40)") (class "Default")
      (node (ref "J221") (pin "40") (pinfunction "40_40") (pintype "passive+no_connect"))
    )
    (net (code "154") (name "unconnected-(J222-Pad39)") (class "Default")
      (node (ref "J222") (pin "39") (pinfunction "39_39") (pintype "passive+no_connect"))
    )
    (net (code "155") (name "unconnected-(J222-Pad40)") (class "Default")
      (node (ref "J222") (pin "40") (pinfunction "40_40") (pintype "passive+no_connect"))
    )
  )
)
